# pCog104_Tester.net
KiCad netlist of a schematic drawn in EAGLE
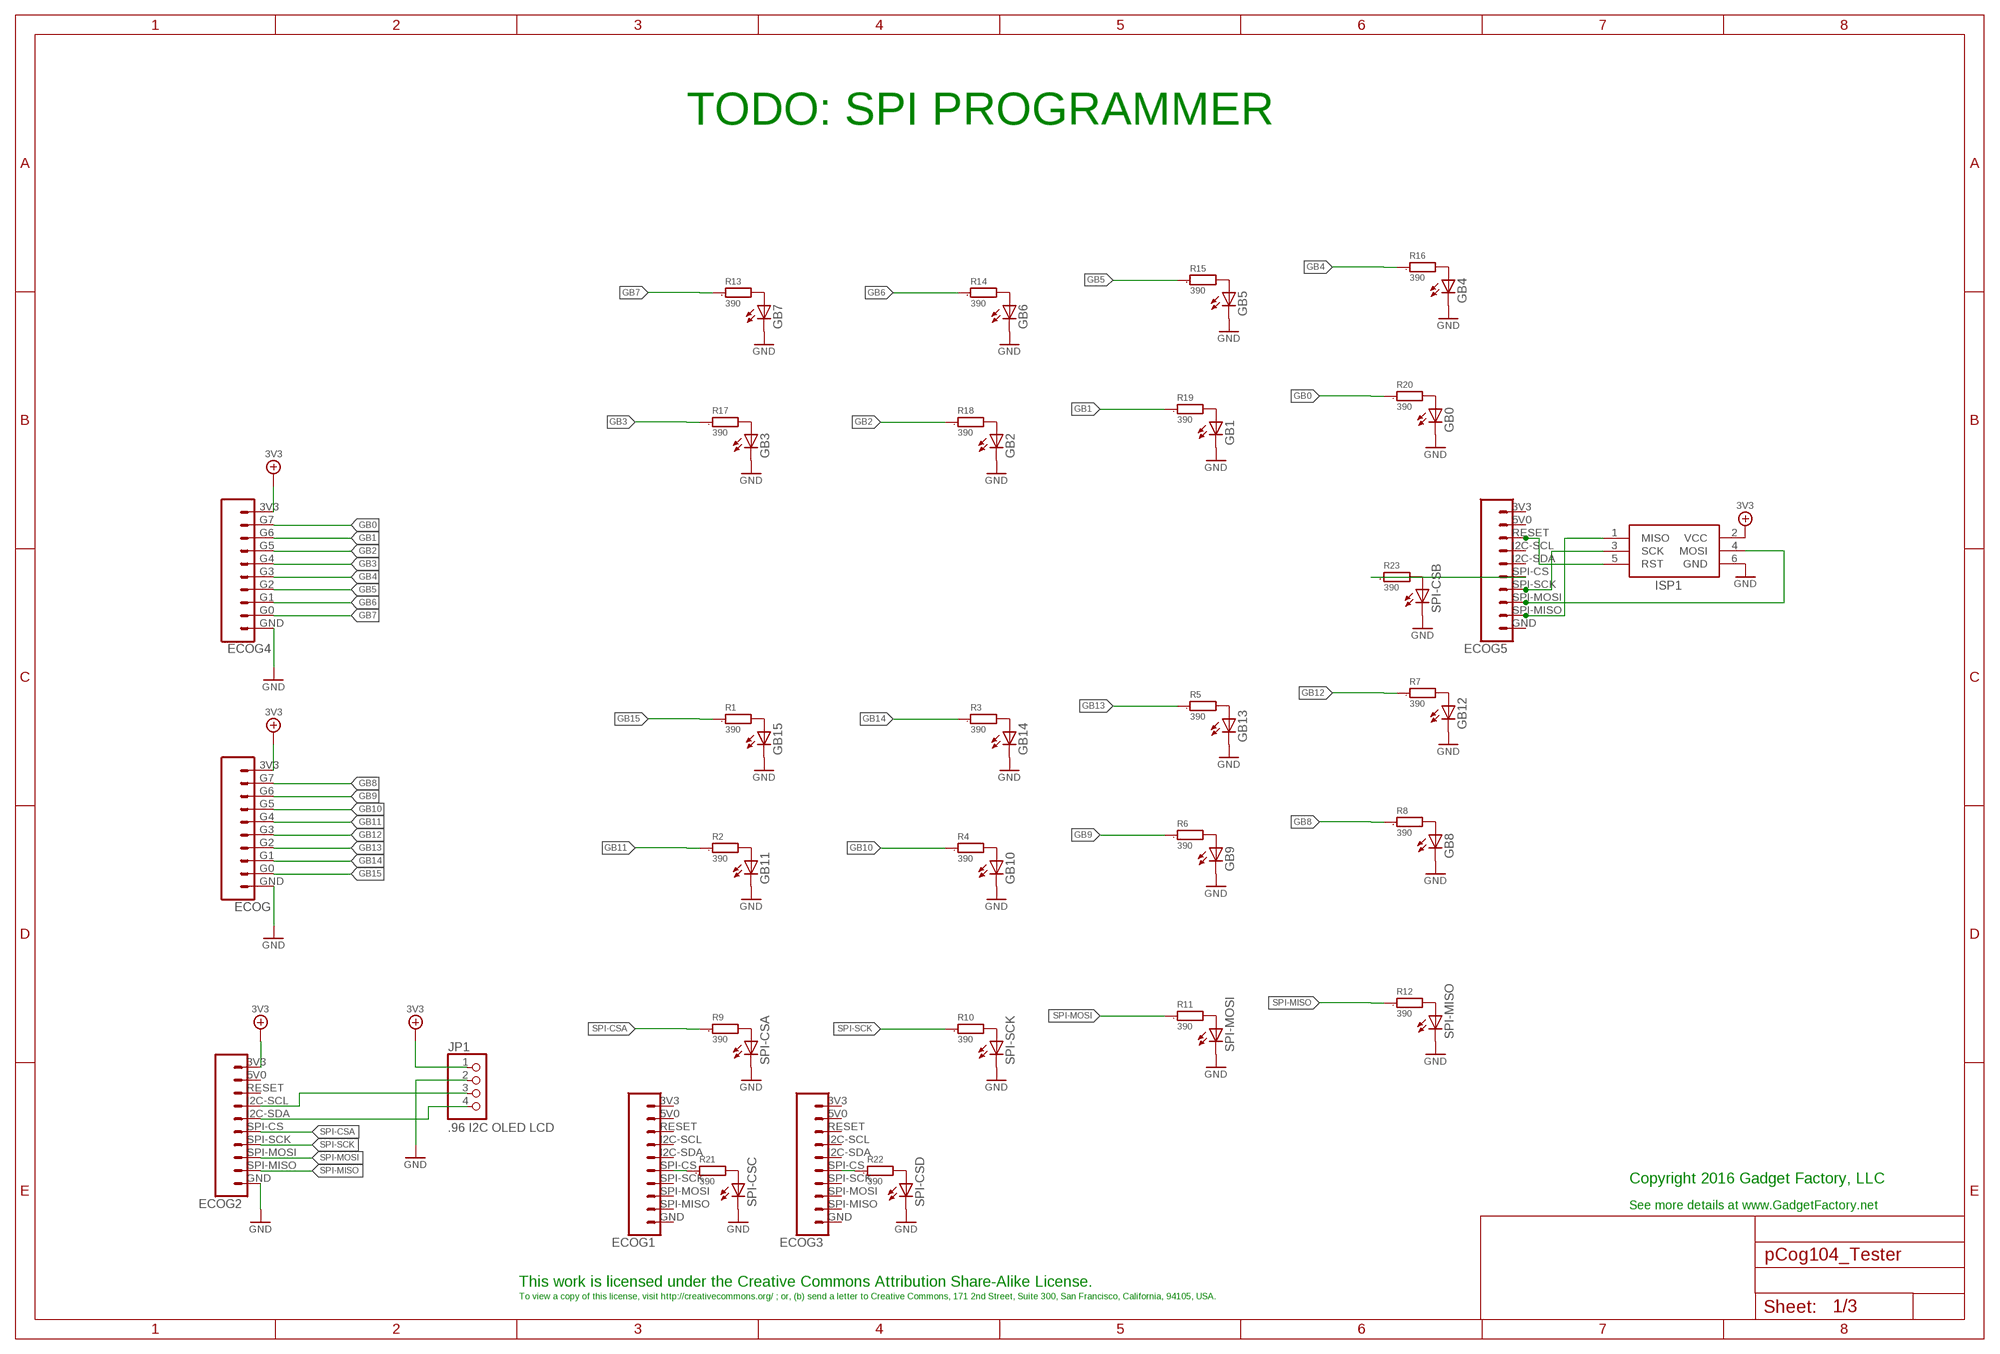
[diagram p0: schematic, sheet 1]
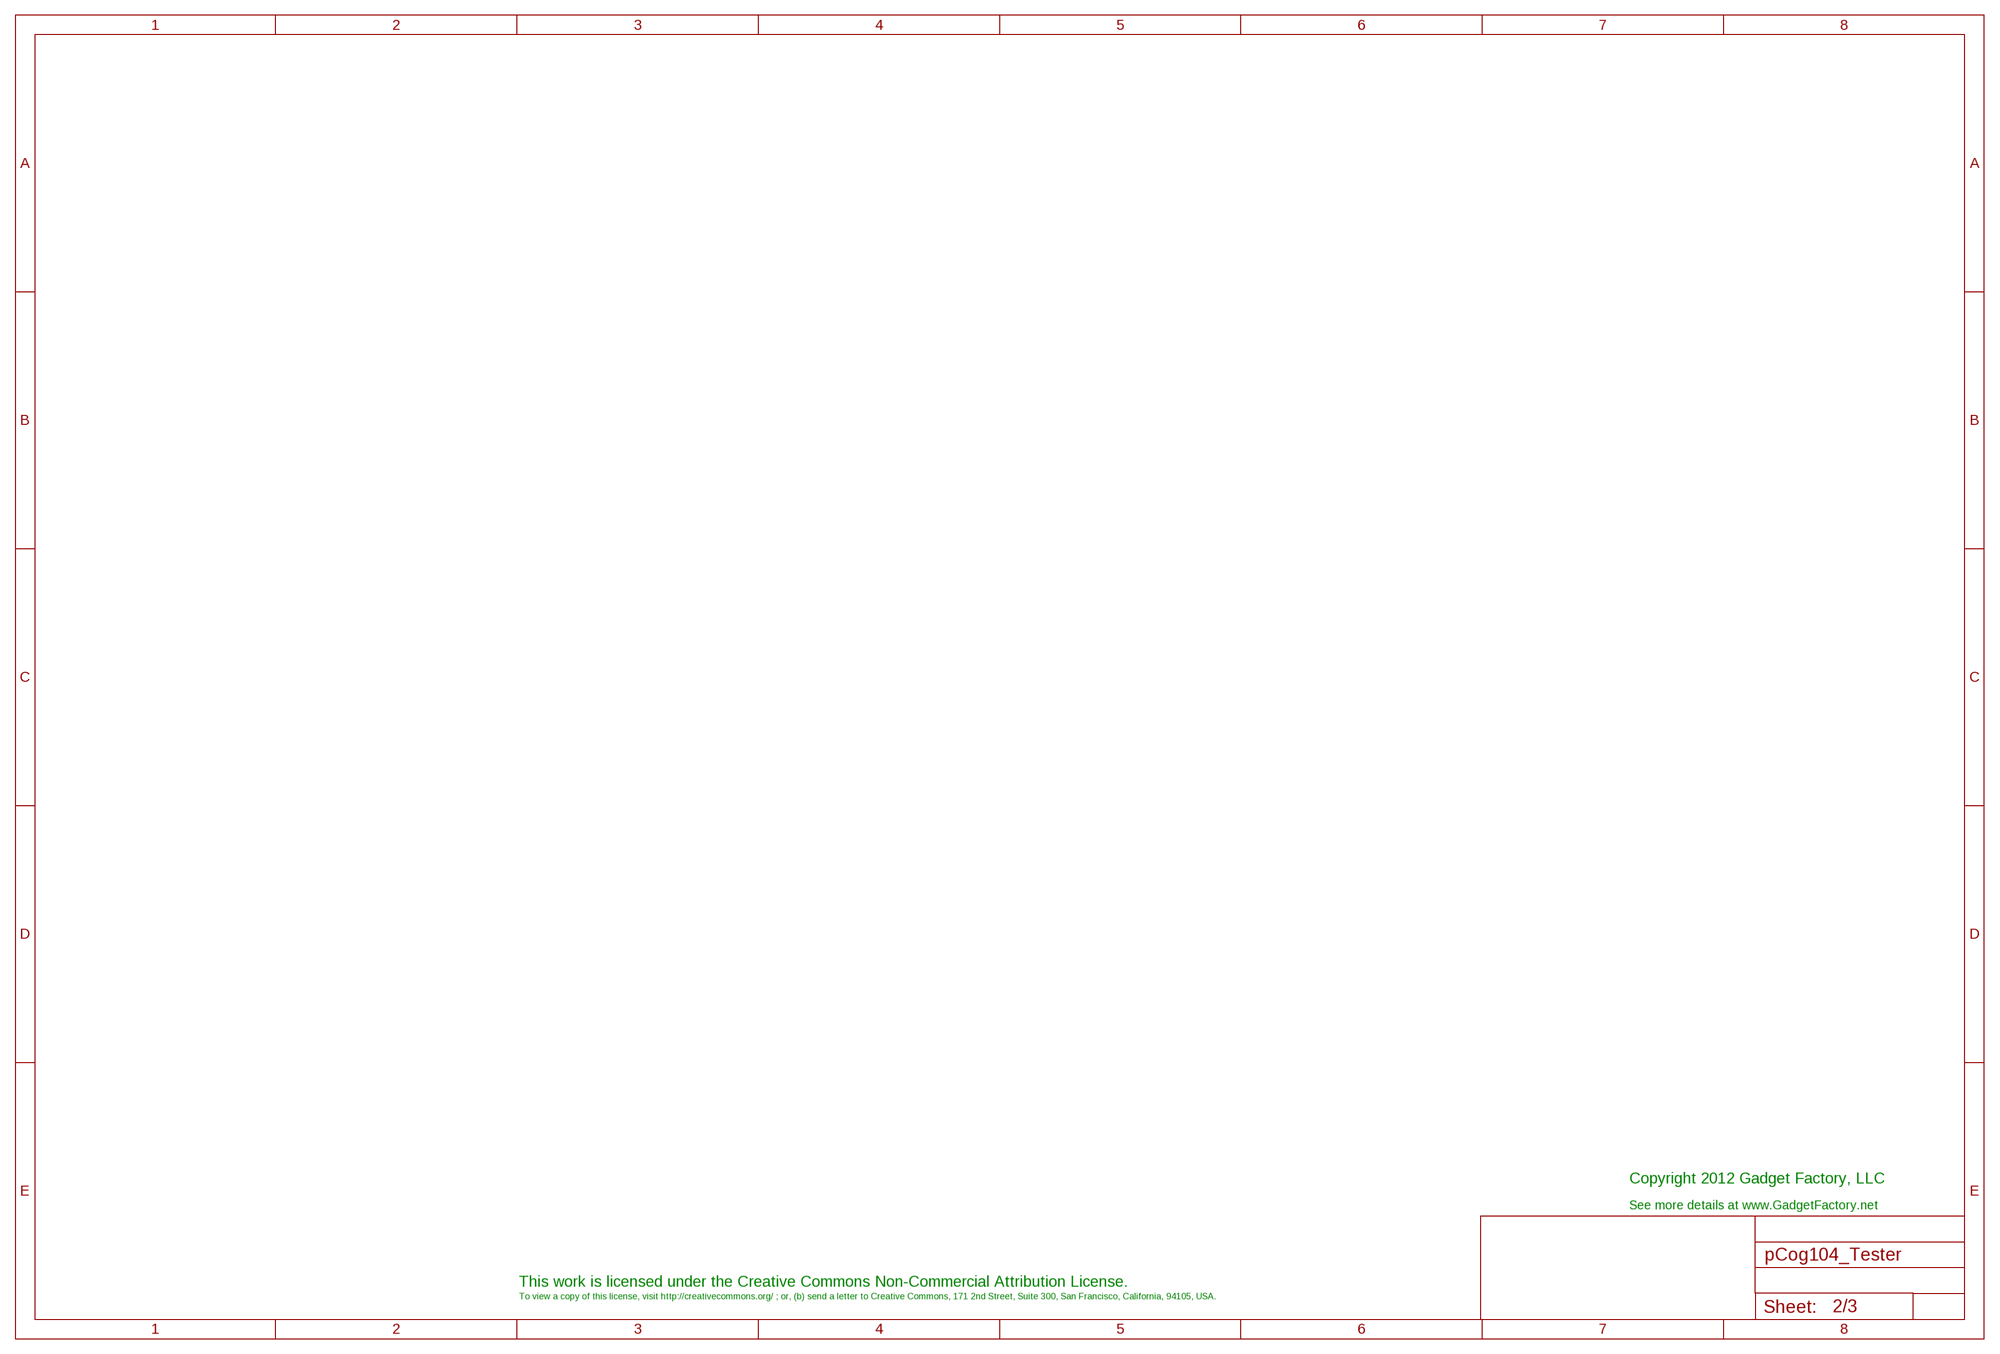
[diagram p1: schematic, sheet 2]
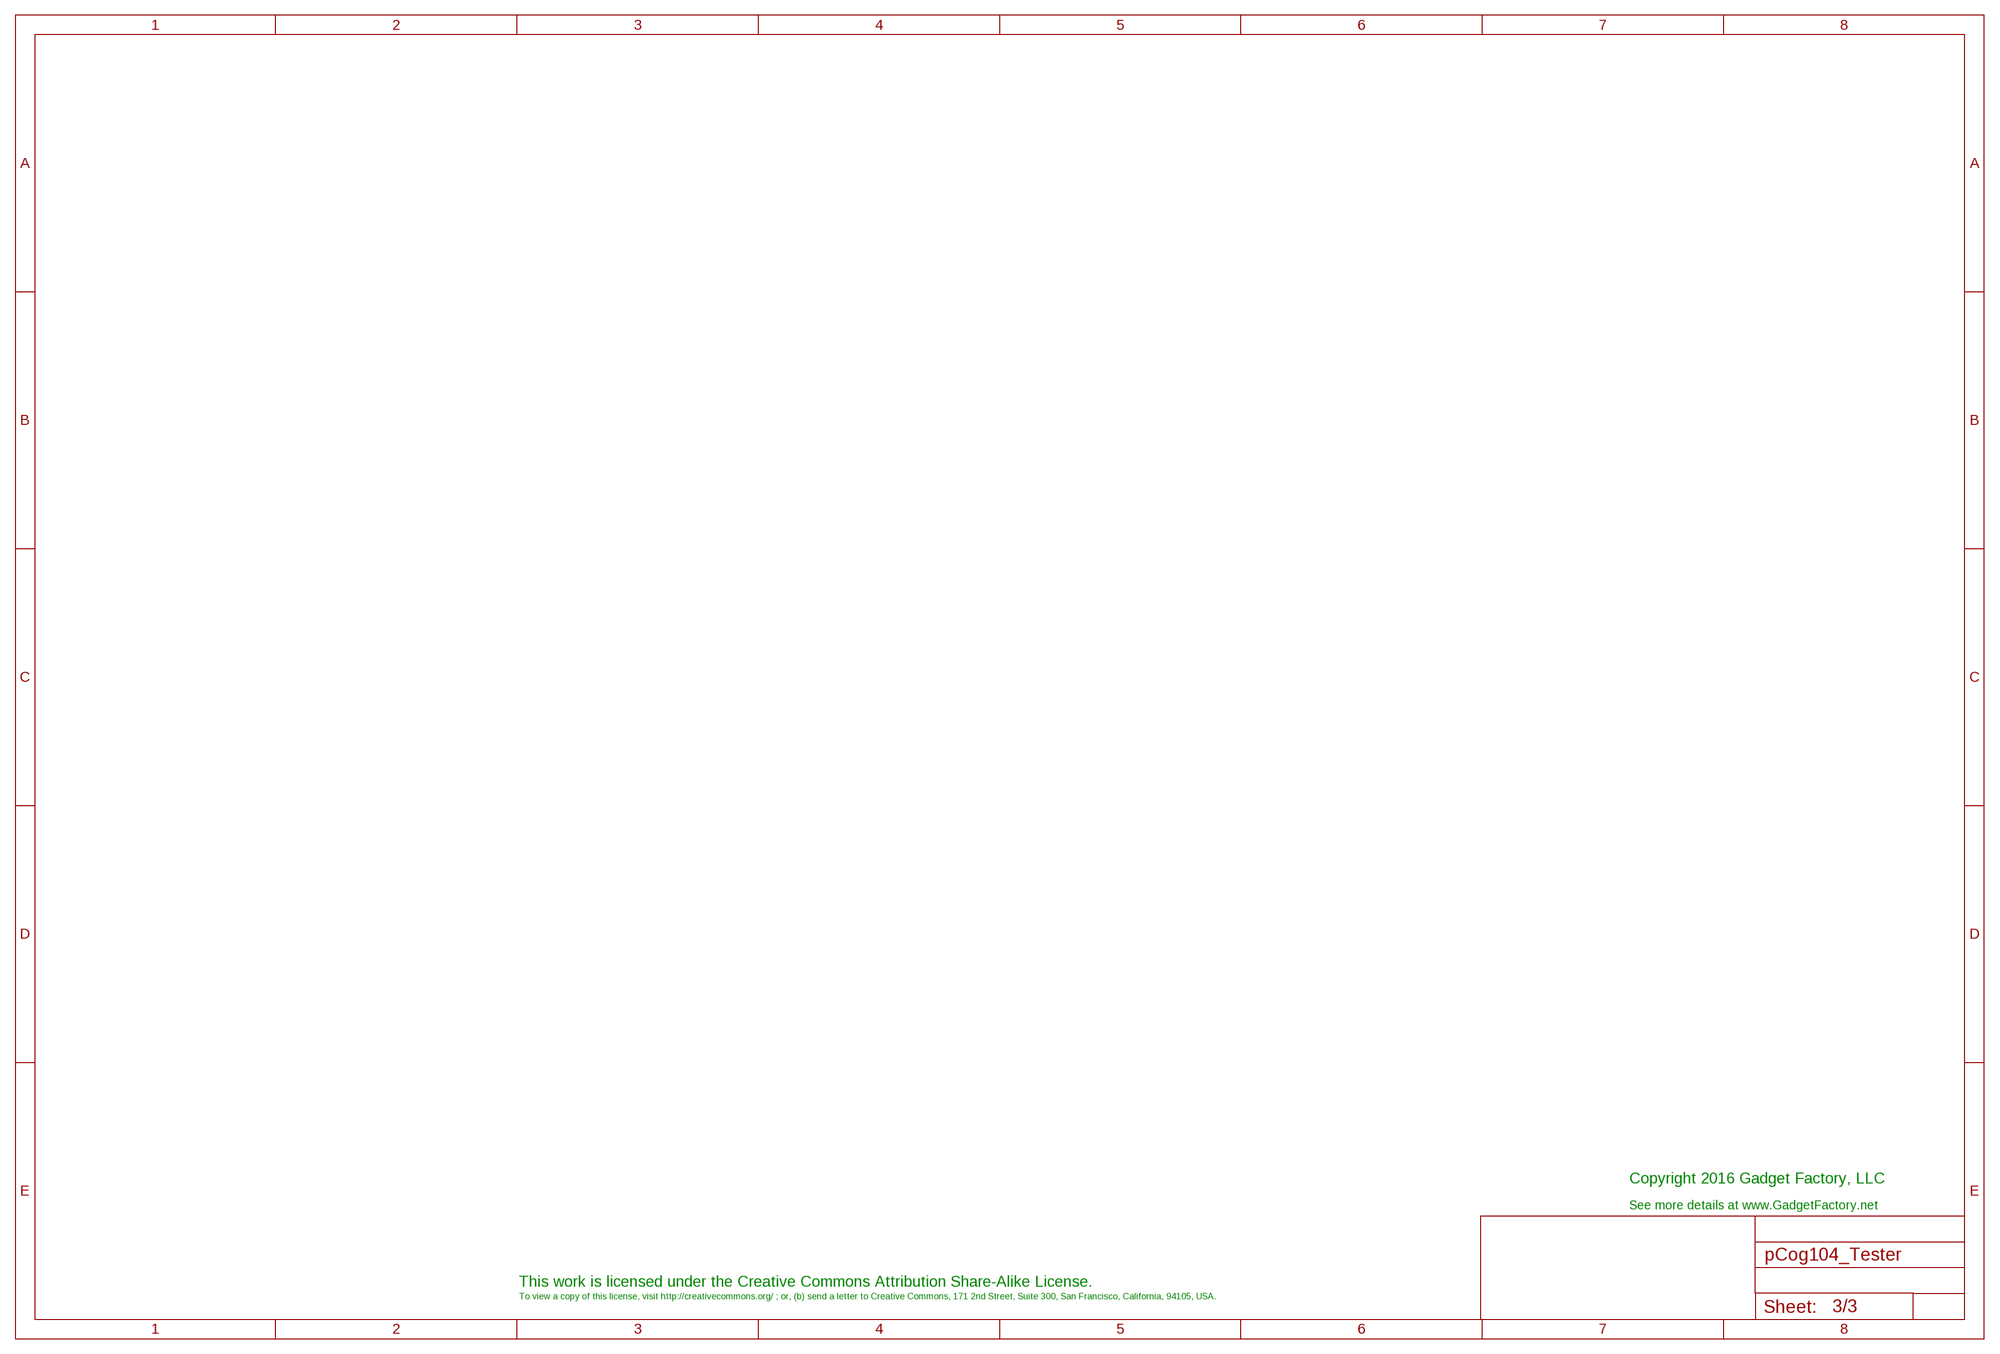
[diagram p2: schematic, sheet 3]

(export (version "E")
  (design (tool "Eeschema 10.0.6"))
  (components
    (comp (ref "ECOG")
      (value "ECOG_GENERAL_ROWTHROUGHOLE")
      (footprint "eagle-import:ECOG_GENERAL_TH")
      (libsource (lib "eagle-import") (part "ECOG_GENERAL_ROWTHROUGHOLE"))
    )
    (comp (ref "ECOG1")
      (value "ECOG_BUSES_ROWTHROUGHHOLE")
      (footprint "eagle-import:ECOG_BUSES_TH")
      (libsource (lib "eagle-import") (part "ECOG_BUSES_ROWTHROUGHHOLE"))
    )
    (comp (ref "ECOG2")
      (value "ECOG_BUSES_ROWTHROUGHHOLE")
      (footprint "eagle-import:ECOG_BUSES_TH")
      (libsource (lib "eagle-import") (part "ECOG_BUSES_ROWTHROUGHHOLE"))
    )
    (comp (ref "ECOG3")
      (value "ECOG_BUSES_ROWTHROUGHHOLE")
      (footprint "eagle-import:ECOG_BUSES_TH")
      (libsource (lib "eagle-import") (part "ECOG_BUSES_ROWTHROUGHHOLE"))
    )
    (comp (ref "ECOG4")
      (value "ECOG_GENERAL_ROWTHROUGHOLE")
      (footprint "eagle-import:ECOG_GENERAL_TH")
      (libsource (lib "eagle-import") (part "ECOG_GENERAL_ROWTHROUGHOLE"))
    )
    (comp (ref "ECOG5")
      (value "ECOG_BUSES_ROWTHROUGHHOLE")
      (footprint "eagle-import:ECOG_BUSES_TH")
      (libsource (lib "eagle-import") (part "ECOG_BUSES_ROWTHROUGHHOLE"))
    )
    (comp (ref "GB0")
      (value "LEDCHIP-LED0805")
      (footprint "eagle-import:CHIP-LED0805")
      (fields
        (field (name "PARTNO") "LTST-C170KGKT,LITE-ON INC (VA),DK,160-1414-1-ND,LED GREEN CLEAR 0805 SMD, REF17")
      )
      (libsource (lib "eagle-import") (part "LEDCHIP-LED0805"))
    )
    (comp (ref "GB1")
      (value "LEDCHIP-LED0805")
      (footprint "eagle-import:CHIP-LED0805")
      (fields
        (field (name "PARTNO") "LTST-C170KGKT,LITE-ON INC (VA),DK,160-1414-1-ND,LED GREEN CLEAR 0805 SMD, REF17")
      )
      (libsource (lib "eagle-import") (part "LEDCHIP-LED0805"))
    )
    (comp (ref "GB2")
      (value "LEDCHIP-LED0805")
      (footprint "eagle-import:CHIP-LED0805")
      (fields
        (field (name "PARTNO") "LTST-C170KGKT,LITE-ON INC (VA),DK,160-1414-1-ND,LED GREEN CLEAR 0805 SMD, REF17")
      )
      (libsource (lib "eagle-import") (part "LEDCHIP-LED0805"))
    )
    (comp (ref "GB3")
      (value "LEDCHIP-LED0805")
      (footprint "eagle-import:CHIP-LED0805")
      (fields
        (field (name "PARTNO") "LTST-C170KGKT,LITE-ON INC (VA),DK,160-1414-1-ND,LED GREEN CLEAR 0805 SMD, REF17")
      )
      (libsource (lib "eagle-import") (part "LEDCHIP-LED0805"))
    )
    (comp (ref "GB4")
      (value "LEDCHIP-LED0805")
      (footprint "eagle-import:CHIP-LED0805")
      (fields
        (field (name "PARTNO") "LTST-C170KGKT,LITE-ON INC (VA),DK,160-1414-1-ND,LED GREEN CLEAR 0805 SMD, REF17")
      )
      (libsource (lib "eagle-import") (part "LEDCHIP-LED0805"))
    )
    (comp (ref "GB5")
      (value "LEDCHIP-LED0805")
      (footprint "eagle-import:CHIP-LED0805")
      (fields
        (field (name "PARTNO") "LTST-C170KGKT,LITE-ON INC (VA),DK,160-1414-1-ND,LED GREEN CLEAR 0805 SMD, REF17")
      )
      (libsource (lib "eagle-import") (part "LEDCHIP-LED0805"))
    )
    (comp (ref "GB6")
      (value "LEDCHIP-LED0805")
      (footprint "eagle-import:CHIP-LED0805")
      (fields
        (field (name "PARTNO") "LTST-C170KGKT,LITE-ON INC (VA),DK,160-1414-1-ND,LED GREEN CLEAR 0805 SMD, REF17")
      )
      (libsource (lib "eagle-import") (part "LEDCHIP-LED0805"))
    )
    (comp (ref "GB7")
      (value "LEDCHIP-LED0805")
      (footprint "eagle-import:CHIP-LED0805")
      (fields
        (field (name "PARTNO") "LTST-C170KGKT,LITE-ON INC (VA),DK,160-1414-1-ND,LED GREEN CLEAR 0805 SMD, REF17")
      )
      (libsource (lib "eagle-import") (part "LEDCHIP-LED0805"))
    )
    (comp (ref "GB8")
      (value "LEDCHIP-LED0805")
      (footprint "eagle-import:CHIP-LED0805")
      (fields
        (field (name "PARTNO") "LTST-C170KGKT,LITE-ON INC (VA),DK,160-1414-1-ND,LED GREEN CLEAR 0805 SMD, REF17")
      )
      (libsource (lib "eagle-import") (part "LEDCHIP-LED0805"))
    )
    (comp (ref "GB9")
      (value "LEDCHIP-LED0805")
      (footprint "eagle-import:CHIP-LED0805")
      (fields
        (field (name "PARTNO") "LTST-C170KGKT,LITE-ON INC (VA),DK,160-1414-1-ND,LED GREEN CLEAR 0805 SMD, REF17")
      )
      (libsource (lib "eagle-import") (part "LEDCHIP-LED0805"))
    )
    (comp (ref "GB10")
      (value "LEDCHIP-LED0805")
      (footprint "eagle-import:CHIP-LED0805")
      (fields
        (field (name "PARTNO") "LTST-C170KGKT,LITE-ON INC (VA),DK,160-1414-1-ND,LED GREEN CLEAR 0805 SMD, REF17")
      )
      (libsource (lib "eagle-import") (part "LEDCHIP-LED0805"))
    )
    (comp (ref "GB11")
      (value "LEDCHIP-LED0805")
      (footprint "eagle-import:CHIP-LED0805")
      (fields
        (field (name "PARTNO") "LTST-C170KGKT,LITE-ON INC (VA),DK,160-1414-1-ND,LED GREEN CLEAR 0805 SMD, REF17")
      )
      (libsource (lib "eagle-import") (part "LEDCHIP-LED0805"))
    )
    (comp (ref "GB12")
      (value "LEDCHIP-LED0805")
      (footprint "eagle-import:CHIP-LED0805")
      (fields
        (field (name "PARTNO") "LTST-C170KGKT,LITE-ON INC (VA),DK,160-1414-1-ND,LED GREEN CLEAR 0805 SMD, REF17")
      )
      (libsource (lib "eagle-import") (part "LEDCHIP-LED0805"))
    )
    (comp (ref "GB13")
      (value "LEDCHIP-LED0805")
      (footprint "eagle-import:CHIP-LED0805")
      (fields
        (field (name "PARTNO") "LTST-C170KGKT,LITE-ON INC (VA),DK,160-1414-1-ND,LED GREEN CLEAR 0805 SMD, REF17")
      )
      (libsource (lib "eagle-import") (part "LEDCHIP-LED0805"))
    )
    (comp (ref "GB14")
      (value "LEDCHIP-LED0805")
      (footprint "eagle-import:CHIP-LED0805")
      (fields
        (field (name "PARTNO") "LTST-C170KGKT,LITE-ON INC (VA),DK,160-1414-1-ND,LED GREEN CLEAR 0805 SMD, REF17")
      )
      (libsource (lib "eagle-import") (part "LEDCHIP-LED0805"))
    )
    (comp (ref "GB15")
      (value "LEDCHIP-LED0805")
      (footprint "eagle-import:CHIP-LED0805")
      (fields
        (field (name "PARTNO") "LTST-C170KGKT,LITE-ON INC (VA),DK,160-1414-1-ND,LED GREEN CLEAR 0805 SMD, REF17")
      )
      (libsource (lib "eagle-import") (part "LEDCHIP-LED0805"))
    )
    (comp (ref "ISP1")
      (value "AVRISP-6")
      (footprint "eagle-import:AVRISP")
      (libsource (lib "eagle-import") (part "AVRISP-6"))
    )
    (comp (ref "JP1")
      (value ".96 I2C OLED LCD")
      (footprint "eagle-import:1X04")
      (libsource (lib "eagle-import") (part "PINHD-1X4"))
    )
    (comp (ref "R1")
      (value "390")
      (footprint "eagle-import:0805")
      (libsource (lib "eagle-import") (part "R0805"))
    )
    (comp (ref "R2")
      (value "390")
      (footprint "eagle-import:0805")
      (libsource (lib "eagle-import") (part "R0805"))
    )
    (comp (ref "R3")
      (value "390")
      (footprint "eagle-import:0805")
      (libsource (lib "eagle-import") (part "R0805"))
    )
    (comp (ref "R4")
      (value "390")
      (footprint "eagle-import:0805")
      (libsource (lib "eagle-import") (part "R0805"))
    )
    (comp (ref "R5")
      (value "390")
      (footprint "eagle-import:0805")
      (libsource (lib "eagle-import") (part "R0805"))
    )
    (comp (ref "R6")
      (value "390")
      (footprint "eagle-import:0805")
      (libsource (lib "eagle-import") (part "R0805"))
    )
    (comp (ref "R7")
      (value "390")
      (footprint "eagle-import:0805")
      (libsource (lib "eagle-import") (part "R0805"))
    )
    (comp (ref "R8")
      (value "390")
      (footprint "eagle-import:0805")
      (libsource (lib "eagle-import") (part "R0805"))
    )
    (comp (ref "R9")
      (value "390")
      (footprint "eagle-import:0805")
      (libsource (lib "eagle-import") (part "R0805"))
    )
    (comp (ref "R10")
      (value "390")
      (footprint "eagle-import:0805")
      (libsource (lib "eagle-import") (part "R0805"))
    )
    (comp (ref "R11")
      (value "390")
      (footprint "eagle-import:0805")
      (libsource (lib "eagle-import") (part "R0805"))
    )
    (comp (ref "R12")
      (value "390")
      (footprint "eagle-import:0805")
      (libsource (lib "eagle-import") (part "R0805"))
    )
    (comp (ref "R13")
      (value "390")
      (footprint "eagle-import:0805")
      (libsource (lib "eagle-import") (part "R0805"))
    )
    (comp (ref "R14")
      (value "390")
      (footprint "eagle-import:0805")
      (libsource (lib "eagle-import") (part "R0805"))
    )
    (comp (ref "R15")
      (value "390")
      (footprint "eagle-import:0805")
      (libsource (lib "eagle-import") (part "R0805"))
    )
    (comp (ref "R16")
      (value "390")
      (footprint "eagle-import:0805")
      (libsource (lib "eagle-import") (part "R0805"))
    )
    (comp (ref "R17")
      (value "390")
      (footprint "eagle-import:0805")
      (libsource (lib "eagle-import") (part "R0805"))
    )
    (comp (ref "R18")
      (value "390")
      (footprint "eagle-import:0805")
      (libsource (lib "eagle-import") (part "R0805"))
    )
    (comp (ref "R19")
      (value "390")
      (footprint "eagle-import:0805")
      (libsource (lib "eagle-import") (part "R0805"))
    )
    (comp (ref "R20")
      (value "390")
      (footprint "eagle-import:0805")
      (libsource (lib "eagle-import") (part "R0805"))
    )
    (comp (ref "R21")
      (value "390")
      (footprint "eagle-import:0805")
      (libsource (lib "eagle-import") (part "R0805"))
    )
    (comp (ref "R22")
      (value "390")
      (footprint "eagle-import:0805")
      (libsource (lib "eagle-import") (part "R0805"))
    )
    (comp (ref "R23")
      (value "390")
      (footprint "eagle-import:0805")
      (libsource (lib "eagle-import") (part "R0805"))
    )
    (comp (ref "SPI-CSA")
      (value "LEDCHIP-LED0805")
      (footprint "eagle-import:CHIP-LED0805")
      (fields
        (field (name "PARTNO") "LTST-C170KGKT,LITE-ON INC (VA),DK,160-1414-1-ND,LED GREEN CLEAR 0805 SMD, REF17")
      )
      (libsource (lib "eagle-import") (part "LEDCHIP-LED0805"))
    )
    (comp (ref "SPI-CSB")
      (value "LEDCHIP-LED0805")
      (footprint "eagle-import:CHIP-LED0805")
      (fields
        (field (name "PARTNO") "LTST-C170KGKT,LITE-ON INC (VA),DK,160-1414-1-ND,LED GREEN CLEAR 0805 SMD, REF17")
      )
      (libsource (lib "eagle-import") (part "LEDCHIP-LED0805"))
    )
    (comp (ref "SPI-CSC")
      (value "LEDCHIP-LED0805")
      (footprint "eagle-import:CHIP-LED0805")
      (fields
        (field (name "PARTNO") "LTST-C170KGKT,LITE-ON INC (VA),DK,160-1414-1-ND,LED GREEN CLEAR 0805 SMD, REF17")
      )
      (libsource (lib "eagle-import") (part "LEDCHIP-LED0805"))
    )
    (comp (ref "SPI-CSD")
      (value "LEDCHIP-LED0805")
      (footprint "eagle-import:CHIP-LED0805")
      (fields
        (field (name "PARTNO") "LTST-C170KGKT,LITE-ON INC (VA),DK,160-1414-1-ND,LED GREEN CLEAR 0805 SMD, REF17")
      )
      (libsource (lib "eagle-import") (part "LEDCHIP-LED0805"))
    )
    (comp (ref "SPI-MISO")
      (value "LEDCHIP-LED0805")
      (footprint "eagle-import:CHIP-LED0805")
      (fields
        (field (name "PARTNO") "LTST-C170KGKT,LITE-ON INC (VA),DK,160-1414-1-ND,LED GREEN CLEAR 0805 SMD, REF17")
      )
      (libsource (lib "eagle-import") (part "LEDCHIP-LED0805"))
    )
    (comp (ref "SPI-MOSI")
      (value "LEDCHIP-LED0805")
      (footprint "eagle-import:CHIP-LED0805")
      (fields
        (field (name "PARTNO") "LTST-C170KGKT,LITE-ON INC (VA),DK,160-1414-1-ND,LED GREEN CLEAR 0805 SMD, REF17")
      )
      (libsource (lib "eagle-import") (part "LEDCHIP-LED0805"))
    )
    (comp (ref "SPI-SCK")
      (value "LEDCHIP-LED0805")
      (footprint "eagle-import:CHIP-LED0805")
      (fields
        (field (name "PARTNO") "LTST-C170KGKT,LITE-ON INC (VA),DK,160-1414-1-ND,LED GREEN CLEAR 0805 SMD, REF17")
      )
      (libsource (lib "eagle-import") (part "LEDCHIP-LED0805"))
    )
  )
  (nets
    (net (code "1") (name "3V3") (class "Default")
      (node (ref "ECOG") (pin "3V3") (pinfunction "3V3_3V3") (pintype "power_in"))
      (node (ref "ECOG2") (pin "3V3") (pinfunction "3V3_3V3") (pintype "passive"))
      (node (ref "ECOG4") (pin "3V3") (pinfunction "3V3_3V3") (pintype "power_in"))
      (node (ref "ISP1") (pin "2") (pinfunction "VCC_2") (pintype "power_in"))
      (node (ref "JP1") (pin "1") (pinfunction "1_1") (pintype "passive"))
    )
    (net (code "2") (name "GB0") (class "Default")
      (node (ref "ECOG4") (pin "G7") (pinfunction "G7_G7") (pintype "passive"))
      (node (ref "R20") (pin "1") (pinfunction "1_1") (pintype "passive"))
    )
    (net (code "3") (name "GB1") (class "Default")
      (node (ref "ECOG4") (pin "G6") (pinfunction "G6_G6") (pintype "passive"))
      (node (ref "R19") (pin "1") (pinfunction "1_1") (pintype "passive"))
    )
    (net (code "4") (name "GB2") (class "Default")
      (node (ref "ECOG4") (pin "G5") (pinfunction "G5_G5") (pintype "passive"))
      (node (ref "R18") (pin "1") (pinfunction "1_1") (pintype "passive"))
    )
    (net (code "5") (name "GB3") (class "Default")
      (node (ref "ECOG4") (pin "G4") (pinfunction "G4_G4") (pintype "passive"))
      (node (ref "R17") (pin "1") (pinfunction "1_1") (pintype "passive"))
    )
    (net (code "6") (name "GB4") (class "Default")
      (node (ref "ECOG4") (pin "G3") (pinfunction "G3_G3") (pintype "passive"))
      (node (ref "R16") (pin "1") (pinfunction "1_1") (pintype "passive"))
    )
    (net (code "7") (name "GB5") (class "Default")
      (node (ref "ECOG4") (pin "G2") (pinfunction "G2_G2") (pintype "passive"))
      (node (ref "R15") (pin "1") (pinfunction "1_1") (pintype "passive"))
    )
    (net (code "8") (name "GB6") (class "Default")
      (node (ref "ECOG4") (pin "G1") (pinfunction "G1_G1") (pintype "passive"))
      (node (ref "R14") (pin "1") (pinfunction "1_1") (pintype "passive"))
    )
    (net (code "9") (name "GB7") (class "Default")
      (node (ref "ECOG4") (pin "G0") (pinfunction "G0_G0") (pintype "passive"))
      (node (ref "R13") (pin "1") (pinfunction "1_1") (pintype "passive"))
    )
    (net (code "10") (name "GB8") (class "Default")
      (node (ref "ECOG") (pin "G7") (pinfunction "G7_G7") (pintype "passive"))
      (node (ref "R8") (pin "1") (pinfunction "1_1") (pintype "passive"))
    )
    (net (code "11") (name "GB9") (class "Default")
      (node (ref "ECOG") (pin "G6") (pinfunction "G6_G6") (pintype "passive"))
      (node (ref "R6") (pin "1") (pinfunction "1_1") (pintype "passive"))
    )
    (net (code "12") (name "GB10") (class "Default")
      (node (ref "ECOG") (pin "G5") (pinfunction "G5_G5") (pintype "passive"))
      (node (ref "R4") (pin "1") (pinfunction "1_1") (pintype "passive"))
    )
    (net (code "13") (name "GB11") (class "Default")
      (node (ref "ECOG") (pin "G4") (pinfunction "G4_G4") (pintype "passive"))
      (node (ref "R2") (pin "1") (pinfunction "1_1") (pintype "passive"))
    )
    (net (code "14") (name "GB12") (class "Default")
      (node (ref "ECOG") (pin "G3") (pinfunction "G3_G3") (pintype "passive"))
      (node (ref "R7") (pin "1") (pinfunction "1_1") (pintype "passive"))
    )
    (net (code "15") (name "GB13") (class "Default")
      (node (ref "ECOG") (pin "G2") (pinfunction "G2_G2") (pintype "passive"))
      (node (ref "R5") (pin "1") (pinfunction "1_1") (pintype "passive"))
    )
    (net (code "16") (name "GB14") (class "Default")
      (node (ref "ECOG") (pin "G1") (pinfunction "G1_G1") (pintype "passive"))
      (node (ref "R3") (pin "1") (pinfunction "1_1") (pintype "passive"))
    )
    (net (code "17") (name "GB15") (class "Default")
      (node (ref "ECOG") (pin "G0") (pinfunction "G0_G0") (pintype "passive"))
      (node (ref "R1") (pin "1") (pinfunction "1_1") (pintype "passive"))
    )
    (net (code "18") (name "GND") (class "Default")
      (node (ref "ECOG") (pin "GND") (pinfunction "GND_GND") (pintype "power_in"))
      (node (ref "ECOG2") (pin "GND") (pinfunction "GND_GND") (pintype "passive"))
      (node (ref "ECOG4") (pin "GND") (pinfunction "GND_GND") (pintype "power_in"))
      (node (ref "GB0") (pin "C") (pinfunction "C_C") (pintype "passive"))
      (node (ref "GB1") (pin "C") (pinfunction "C_C") (pintype "passive"))
      (node (ref "GB10") (pin "C") (pinfunction "C_C") (pintype "passive"))
      (node (ref "GB11") (pin "C") (pinfunction "C_C") (pintype "passive"))
      (node (ref "GB12") (pin "C") (pinfunction "C_C") (pintype "passive"))
      (node (ref "GB13") (pin "C") (pinfunction "C_C") (pintype "passive"))
      (node (ref "GB14") (pin "C") (pinfunction "C_C") (pintype "passive"))
      (node (ref "GB15") (pin "C") (pinfunction "C_C") (pintype "passive"))
      (node (ref "GB2") (pin "C") (pinfunction "C_C") (pintype "passive"))
      (node (ref "GB3") (pin "C") (pinfunction "C_C") (pintype "passive"))
      (node (ref "GB4") (pin "C") (pinfunction "C_C") (pintype "passive"))
      (node (ref "GB5") (pin "C") (pinfunction "C_C") (pintype "passive"))
      (node (ref "GB6") (pin "C") (pinfunction "C_C") (pintype "passive"))
      (node (ref "GB7") (pin "C") (pinfunction "C_C") (pintype "passive"))
      (node (ref "GB8") (pin "C") (pinfunction "C_C") (pintype "passive"))
      (node (ref "GB9") (pin "C") (pinfunction "C_C") (pintype "passive"))
      (node (ref "ISP1") (pin "6") (pinfunction "GND_6") (pintype "power_in"))
      (node (ref "JP1") (pin "2") (pinfunction "2_2") (pintype "passive"))
      (node (ref "SPI-CSA") (pin "C") (pinfunction "C_C") (pintype "passive"))
      (node (ref "SPI-CSB") (pin "C") (pinfunction "C_C") (pintype "passive"))
      (node (ref "SPI-CSC") (pin "C") (pinfunction "C_C") (pintype "passive"))
      (node (ref "SPI-CSD") (pin "C") (pinfunction "C_C") (pintype "passive"))
      (node (ref "SPI-MISO") (pin "C") (pinfunction "C_C") (pintype "passive"))
      (node (ref "SPI-MOSI") (pin "C") (pinfunction "C_C") (pintype "passive"))
      (node (ref "SPI-SCK") (pin "C") (pinfunction "C_C") (pintype "passive"))
    )
    (net (code "19") (name "Net-(ECOG1-PadSPI-CS)") (class "Default")
      (node (ref "ECOG1") (pin "SPI-CS") (pinfunction "SPI-CS_SPI-CS") (pintype "passive"))
      (node (ref "R21") (pin "1") (pinfunction "1_1") (pintype "passive"))
    )
    (net (code "20") (name "Net-(ECOG2-PadI2C-SCL)") (class "Default")
      (node (ref "ECOG2") (pin "I2C-SCL") (pinfunction "I2C-SCL_I2C-SCL") (pintype "passive"))
      (node (ref "JP1") (pin "3") (pinfunction "3_3") (pintype "passive"))
    )
    (net (code "21") (name "Net-(ECOG2-PadI2C-SDA)") (class "Default")
      (node (ref "ECOG2") (pin "I2C-SDA") (pinfunction "I2C-SDA_I2C-SDA") (pintype "passive"))
      (node (ref "JP1") (pin "4") (pinfunction "4_4") (pintype "passive"))
    )
    (net (code "22") (name "Net-(ECOG3-PadSPI-CS)") (class "Default")
      (node (ref "ECOG3") (pin "SPI-CS") (pinfunction "SPI-CS_SPI-CS") (pintype "passive"))
      (node (ref "R22") (pin "1") (pinfunction "1_1") (pintype "passive"))
    )
    (net (code "23") (name "Net-(ECOG5-PadSPI-CS)") (class "Default")
      (node (ref "ECOG5") (pin "SPI-CS") (pinfunction "SPI-CS_SPI-CS") (pintype "passive"))
      (node (ref "R23") (pin "1") (pinfunction "1_1") (pintype "passive"))
    )
    (net (code "24") (name "Net-(GB0-PadA)") (class "Default")
      (node (ref "GB0") (pin "A") (pinfunction "A_A") (pintype "passive"))
      (node (ref "R20") (pin "2") (pinfunction "2_2") (pintype "passive"))
    )
    (net (code "25") (name "Net-(GB1-PadA)") (class "Default")
      (node (ref "GB1") (pin "A") (pinfunction "A_A") (pintype "passive"))
      (node (ref "R19") (pin "2") (pinfunction "2_2") (pintype "passive"))
    )
    (net (code "26") (name "Net-(GB2-PadA)") (class "Default")
      (node (ref "GB2") (pin "A") (pinfunction "A_A") (pintype "passive"))
      (node (ref "R18") (pin "2") (pinfunction "2_2") (pintype "passive"))
    )
    (net (code "27") (name "Net-(GB3-PadA)") (class "Default")
      (node (ref "GB3") (pin "A") (pinfunction "A_A") (pintype "passive"))
      (node (ref "R17") (pin "2") (pinfunction "2_2") (pintype "passive"))
    )
    (net (code "28") (name "Net-(GB4-PadA)") (class "Default")
      (node (ref "GB4") (pin "A") (pinfunction "A_A") (pintype "passive"))
      (node (ref "R16") (pin "2") (pinfunction "2_2") (pintype "passive"))
    )
    (net (code "29") (name "Net-(GB5-PadA)") (class "Default")
      (node (ref "GB5") (pin "A") (pinfunction "A_A") (pintype "passive"))
      (node (ref "R15") (pin "2") (pinfunction "2_2") (pintype "passive"))
    )
    (net (code "30") (name "Net-(GB6-PadA)") (class "Default")
      (node (ref "GB6") (pin "A") (pinfunction "A_A") (pintype "passive"))
      (node (ref "R14") (pin "2") (pinfunction "2_2") (pintype "passive"))
    )
    (net (code "31") (name "Net-(GB7-PadA)") (class "Default")
      (node (ref "GB7") (pin "A") (pinfunction "A_A") (pintype "passive"))
      (node (ref "R13") (pin "2") (pinfunction "2_2") (pintype "passive"))
    )
    (net (code "32") (name "Net-(GB8-PadA)") (class "Default")
      (node (ref "GB8") (pin "A") (pinfunction "A_A") (pintype "passive"))
      (node (ref "R8") (pin "2") (pinfunction "2_2") (pintype "passive"))
    )
    (net (code "33") (name "Net-(GB9-PadA)") (class "Default")
      (node (ref "GB9") (pin "A") (pinfunction "A_A") (pintype "passive"))
      (node (ref "R6") (pin "2") (pinfunction "2_2") (pintype "passive"))
    )
    (net (code "34") (name "Net-(GB10-PadA)") (class "Default")
      (node (ref "GB10") (pin "A") (pinfunction "A_A") (pintype "passive"))
      (node (ref "R4") (pin "2") (pinfunction "2_2") (pintype "passive"))
    )
    (net (code "35") (name "Net-(GB11-PadA)") (class "Default")
      (node (ref "GB11") (pin "A") (pinfunction "A_A") (pintype "passive"))
      (node (ref "R2") (pin "2") (pinfunction "2_2") (pintype "passive"))
    )
    (net (code "36") (name "Net-(GB12-PadA)") (class "Default")
      (node (ref "GB12") (pin "A") (pinfunction "A_A") (pintype "passive"))
      (node (ref "R7") (pin "2") (pinfunction "2_2") (pintype "passive"))
    )
    (net (code "37") (name "Net-(GB13-PadA)") (class "Default")
      (node (ref "GB13") (pin "A") (pinfunction "A_A") (pintype "passive"))
      (node (ref "R5") (pin "2") (pinfunction "2_2") (pintype "passive"))
    )
    (net (code "38") (name "Net-(GB14-PadA)") (class "Default")
      (node (ref "GB14") (pin "A") (pinfunction "A_A") (pintype "passive"))
      (node (ref "R3") (pin "2") (pinfunction "2_2") (pintype "passive"))
    )
    (net (code "39") (name "Net-(GB15-PadA)") (class "Default")
      (node (ref "GB15") (pin "A") (pinfunction "A_A") (pintype "passive"))
      (node (ref "R1") (pin "2") (pinfunction "2_2") (pintype "passive"))
    )
    (net (code "40") (name "Net-(ISP1-MISO)") (class "Default")
      (node (ref "ECOG5") (pin "SPI-MISO") (pinfunction "SPI-MISO_SPI-MISO") (pintype "passive"))
      (node (ref "ISP1") (pin "1") (pinfunction "MISO_1") (pintype "input"))
    )
    (net (code "41") (name "Net-(ISP1-MOSI)") (class "Default")
      (node (ref "ECOG5") (pin "SPI-MOSI") (pinfunction "SPI-MOSI_SPI-MOSI") (pintype "passive"))
      (node (ref "ISP1") (pin "4") (pinfunction "MOSI_4") (pintype "output"))
    )
    (net (code "42") (name "Net-(ISP1-RST)") (class "Default")
      (node (ref "ECOG5") (pin "RESET") (pinfunction "RSV_RESET") (pintype "passive"))
      (node (ref "ISP1") (pin "5") (pinfunction "RST_5") (pintype "output"))
    )
    (net (code "43") (name "Net-(ISP1-SCK)") (class "Default")
      (node (ref "ECOG5") (pin "SPI-SCK") (pinfunction "SPI-SCK_SPI-SCK") (pintype "passive"))
      (node (ref "ISP1") (pin "3") (pinfunction "SCK_3") (pintype "output"))
    )
    (net (code "44") (name "Net-(R9-Pad2)") (class "Default")
      (node (ref "R9") (pin "2") (pinfunction "2_2") (pintype "passive"))
      (node (ref "SPI-CSA") (pin "A") (pinfunction "A_A") (pintype "passive"))
    )
    (net (code "45") (name "Net-(R10-Pad2)") (class "Default")
      (node (ref "R10") (pin "2") (pinfunction "2_2") (pintype "passive"))
      (node (ref "SPI-SCK") (pin "A") (pinfunction "A_A") (pintype "passive"))
    )
    (net (code "46") (name "Net-(R11-Pad2)") (class "Default")
      (node (ref "R11") (pin "2") (pinfunction "2_2") (pintype "passive"))
      (node (ref "SPI-MOSI") (pin "A") (pinfunction "A_A") (pintype "passive"))
    )
    (net (code "47") (name "Net-(R12-Pad2)") (class "Default")
      (node (ref "R12") (pin "2") (pinfunction "2_2") (pintype "passive"))
      (node (ref "SPI-MISO") (pin "A") (pinfunction "A_A") (pintype "passive"))
    )
    (net (code "48") (name "Net-(R21-Pad2)") (class "Default")
      (node (ref "R21") (pin "2") (pinfunction "2_2") (pintype "passive"))
      (node (ref "SPI-CSC") (pin "A") (pinfunction "A_A") (pintype "passive"))
    )
    (net (code "49") (name "Net-(R22-Pad2)") (class "Default")
      (node (ref "R22") (pin "2") (pinfunction "2_2") (pintype "passive"))
      (node (ref "SPI-CSD") (pin "A") (pinfunction "A_A") (pintype "passive"))
    )
    (net (code "50") (name "Net-(R23-Pad2)") (class "Default")
      (node (ref "R23") (pin "2") (pinfunction "2_2") (pintype "passive"))
      (node (ref "SPI-CSB") (pin "A") (pinfunction "A_A") (pintype "passive"))
    )
    (net (code "51") (name "SPI-CSA") (class "Default")
      (node (ref "ECOG2") (pin "SPI-CS") (pinfunction "SPI-CS_SPI-CS") (pintype "passive"))
      (node (ref "R9") (pin "1") (pinfunction "1_1") (pintype "passive"))
    )
    (net (code "52") (name "SPI-MISO") (class "Default")
      (node (ref "ECOG2") (pin "SPI-MISO") (pinfunction "SPI-MISO_SPI-MISO") (pintype "passive"))
      (node (ref "R12") (pin "1") (pinfunction "1_1") (pintype "passive"))
    )
    (net (code "53") (name "SPI-MOSI") (class "Default")
      (node (ref "ECOG2") (pin "SPI-MOSI") (pinfunction "SPI-MOSI_SPI-MOSI") (pintype "passive"))
      (node (ref "R11") (pin "1") (pinfunction "1_1") (pintype "passive"))
    )
    (net (code "54") (name "SPI-SCK") (class "Default")
      (node (ref "ECOG2") (pin "SPI-SCK") (pinfunction "SPI-SCK_SPI-SCK") (pintype "passive"))
      (node (ref "R10") (pin "1") (pinfunction "1_1") (pintype "passive"))
    )
    (net (code "55") (name "unconnected-(ECOG1-Pad3V3)") (class "Default")
      (node (ref "ECOG1") (pin "3V3") (pinfunction "3V3_3V3") (pintype "passive"))
    )
    (net (code "56") (name "unconnected-(ECOG1-PadGND)") (class "Default")
      (node (ref "ECOG1") (pin "GND") (pinfunction "GND_GND") (pintype "passive"))
    )
    (net (code "57") (name "unconnected-(ECOG1-PadI2C-SCL)") (class "Default")
      (node (ref "ECOG1") (pin "I2C-SCL") (pinfunction "I2C-SCL_I2C-SCL") (pintype "passive"))
    )
    (net (code "58") (name "unconnected-(ECOG1-PadI2C-SDA)") (class "Default")
      (node (ref "ECOG1") (pin "I2C-SDA") (pinfunction "I2C-SDA_I2C-SDA") (pintype "passive"))
    )
    (net (code "59") (name "unconnected-(ECOG1-PadSPI-MISO)") (class "Default")
      (node (ref "ECOG1") (pin "SPI-MISO") (pinfunction "SPI-MISO_SPI-MISO") (pintype "passive"))
    )
    (net (code "60") (name "unconnected-(ECOG1-PadSPI-MOSI)") (class "Default")
      (node (ref "ECOG1") (pin "SPI-MOSI") (pinfunction "SPI-MOSI_SPI-MOSI") (pintype "passive"))
    )
    (net (code "61") (name "unconnected-(ECOG1-PadSPI-SCK)") (class "Default")
      (node (ref "ECOG1") (pin "SPI-SCK") (pinfunction "SPI-SCK_SPI-SCK") (pintype "passive"))
    )
    (net (code "62") (name "unconnected-(ECOG1-RSV-Pad5V0)") (class "Default")
      (node (ref "ECOG1") (pin "5V0") (pinfunction "RSV_5V0") (pintype "passive"))
    )
    (net (code "63") (name "unconnected-(ECOG1-RSV-PadRESET)") (class "Default")
      (node (ref "ECOG1") (pin "RESET") (pinfunction "RSV_RESET") (pintype "passive"))
    )
    (net (code "64") (name "unconnected-(ECOG2-RSV-Pad5V0)") (class "Default")
      (node (ref "ECOG2") (pin "5V0") (pinfunction "RSV_5V0") (pintype "passive"))
    )
    (net (code "65") (name "unconnected-(ECOG2-RSV-PadRESET)") (class "Default")
      (node (ref "ECOG2") (pin "RESET") (pinfunction "RSV_RESET") (pintype "passive"))
    )
    (net (code "66") (name "unconnected-(ECOG3-Pad3V3)") (class "Default")
      (node (ref "ECOG3") (pin "3V3") (pinfunction "3V3_3V3") (pintype "passive"))
    )
    (net (code "67") (name "unconnected-(ECOG3-PadGND)") (class "Default")
      (node (ref "ECOG3") (pin "GND") (pinfunction "GND_GND") (pintype "passive"))
    )
    (net (code "68") (name "unconnected-(ECOG3-PadI2C-SCL)") (class "Default")
      (node (ref "ECOG3") (pin "I2C-SCL") (pinfunction "I2C-SCL_I2C-SCL") (pintype "passive"))
    )
    (net (code "69") (name "unconnected-(ECOG3-PadI2C-SDA)") (class "Default")
      (node (ref "ECOG3") (pin "I2C-SDA") (pinfunction "I2C-SDA_I2C-SDA") (pintype "passive"))
    )
    (net (code "70") (name "unconnected-(ECOG3-PadSPI-MISO)") (class "Default")
      (node (ref "ECOG3") (pin "SPI-MISO") (pinfunction "SPI-MISO_SPI-MISO") (pintype "passive"))
    )
    (net (code "71") (name "unconnected-(ECOG3-PadSPI-MOSI)") (class "Default")
      (node (ref "ECOG3") (pin "SPI-MOSI") (pinfunction "SPI-MOSI_SPI-MOSI") (pintype "passive"))
    )
    (net (code "72") (name "unconnected-(ECOG3-PadSPI-SCK)") (class "Default")
      (node (ref "ECOG3") (pin "SPI-SCK") (pinfunction "SPI-SCK_SPI-SCK") (pintype "passive"))
    )
    (net (code "73") (name "unconnected-(ECOG3-RSV-Pad5V0)") (class "Default")
      (node (ref "ECOG3") (pin "5V0") (pinfunction "RSV_5V0") (pintype "passive"))
    )
    (net (code "74") (name "unconnected-(ECOG3-RSV-PadRESET)") (class "Default")
      (node (ref "ECOG3") (pin "RESET") (pinfunction "RSV_RESET") (pintype "passive"))
    )
    (net (code "75") (name "unconnected-(ECOG5-Pad3V3)") (class "Default")
      (node (ref "ECOG5") (pin "3V3") (pinfunction "3V3_3V3") (pintype "passive"))
    )
    (net (code "76") (name "unconnected-(ECOG5-PadGND)") (class "Default")
      (node (ref "ECOG5") (pin "GND") (pinfunction "GND_GND") (pintype "passive"))
    )
    (net (code "77") (name "unconnected-(ECOG5-PadI2C-SCL)") (class "Default")
      (node (ref "ECOG5") (pin "I2C-SCL") (pinfunction "I2C-SCL_I2C-SCL") (pintype "passive"))
    )
    (net (code "78") (name "unconnected-(ECOG5-PadI2C-SDA)") (class "Default")
      (node (ref "ECOG5") (pin "I2C-SDA") (pinfunction "I2C-SDA_I2C-SDA") (pintype "passive"))
    )
    (net (code "79") (name "unconnected-(ECOG5-RSV-Pad5V0)") (class "Default")
      (node (ref "ECOG5") (pin "5V0") (pinfunction "RSV_5V0") (pintype "passive"))
    )
  )
)
